# ir_homekit_1_0.net
KiCad netlist of a schematic drawn in EasyEDA
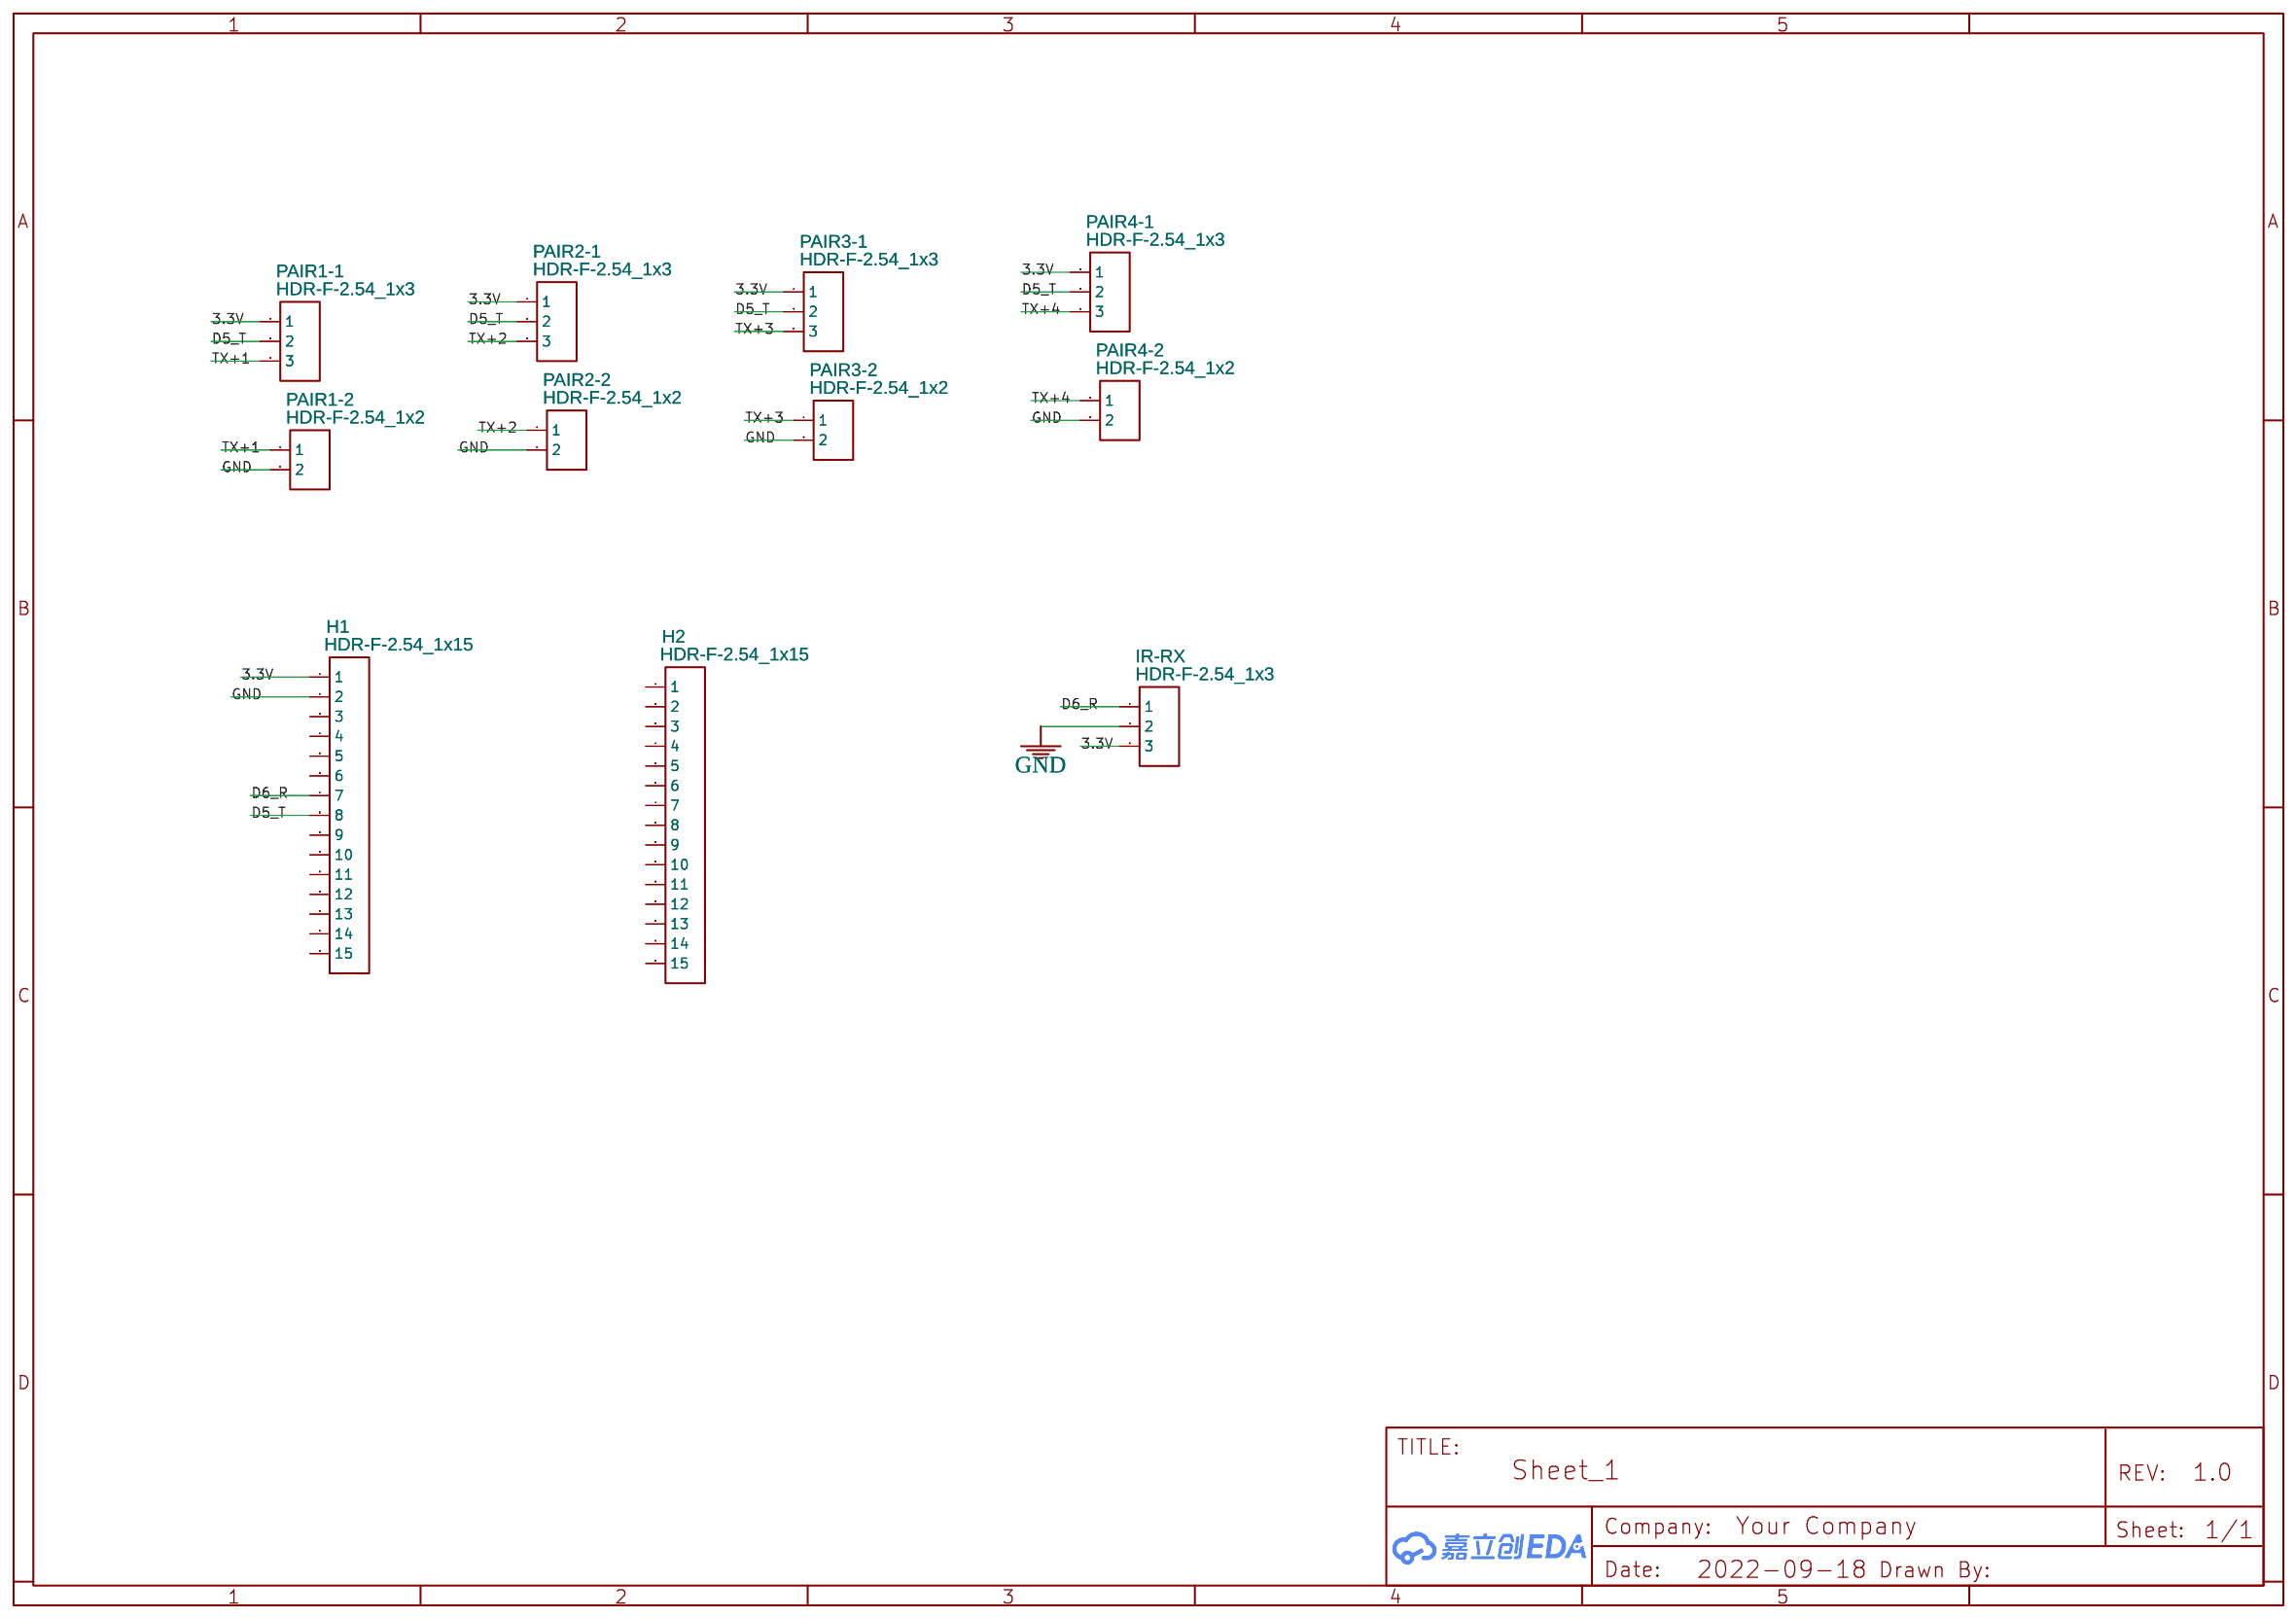
[diagram p0: schematic sheet]

(export (version "E")
  (design (tool "Eeschema 10.0.6"))
  (components
    (comp (ref "H1")
      (value "HDR-F-2.54_1x15")
      (fields (field (name "BOM_Supplier Part") "C124408"))
      (libsource (lib "") (part "HDR-F-2.54_1x15"))
    )
    (comp (ref "H2")
      (value "HDR-F-2.54_1x15")
      (fields (field (name "BOM_Supplier Part") "C124408"))
      (libsource (lib "") (part "HDR-F-2.54_1x15"))
    )
    (comp (ref "IR-RX")
      (value "HDR-F-2.54_1x3")
      (fields (field (name "BOM_Supplier Part") "C146690"))
      (libsource (lib "") (part "HDR-F-2.54_1x3_3"))
    )
    (comp (ref "PAIR1-1")
      (value "HDR-F-2.54_1x3")
      (fields (field (name "BOM_Supplier Part") "C146690"))
      (libsource (lib "") (part "HDR-F-2.54_1x3_2"))
    )
    (comp (ref "PAIR1-2")
      (value "HDR-F-2.54_1x2")
      (fields (field (name "BOM_Supplier Part") "C49661"))
      (libsource (lib "") (part "HDR-F-2.54_1x2_3"))
    )
    (comp (ref "PAIR2-1")
      (value "HDR-F-2.54_1x3")
      (fields (field (name "BOM_Supplier Part") "C146690"))
      (libsource (lib "") (part "HDR-F-2.54_1x3_4"))
    )
    (comp (ref "PAIR2-2")
      (value "HDR-F-2.54_1x2")
      (fields (field (name "BOM_Supplier Part") "C49661"))
      (libsource (lib "") (part "HDR-F-2.54_1x2"))
    )
    (comp (ref "PAIR3-1")
      (value "HDR-F-2.54_1x3")
      (fields (field (name "BOM_Supplier Part") "C146690"))
      (libsource (lib "") (part "HDR-F-2.54_1x3"))
    )
    (comp (ref "PAIR3-2")
      (value "HDR-F-2.54_1x2")
      (fields (field (name "BOM_Supplier Part") "C49661"))
      (libsource (lib "") (part "HDR-F-2.54_1x2_2"))
    )
    (comp (ref "PAIR4-1")
      (value "HDR-F-2.54_1x3")
      (fields (field (name "BOM_Supplier Part") "C146690"))
      (libsource (lib "") (part "HDR-F-2.54_1x3_1"))
    )
    (comp (ref "PAIR4-2")
      (value "HDR-F-2.54_1x2")
      (fields (field (name "BOM_Supplier Part") "C49661"))
      (libsource (lib "") (part "HDR-F-2.54_1x2_1"))
    )
  )
  (nets
    (net (code "1") (name "/3.3V") (class "Default")
      (node (ref "H1") (pin "1") (pinfunction "1_1") (pintype "unspecified"))
      (node (ref "IR-RX") (pin "3") (pinfunction "3_3") (pintype "input"))
      (node (ref "PAIR1-1") (pin "1") (pinfunction "1_1") (pintype "input"))
      (node (ref "PAIR2-1") (pin "1") (pinfunction "1_1") (pintype "input"))
      (node (ref "PAIR3-1") (pin "1") (pinfunction "1_1") (pintype "input"))
      (node (ref "PAIR4-1") (pin "1") (pinfunction "1_1") (pintype "input"))
    )
    (net (code "2") (name "/D5_T") (class "Default")
      (node (ref "H1") (pin "8") (pinfunction "8_8") (pintype "unspecified"))
      (node (ref "PAIR1-1") (pin "2") (pinfunction "2_2") (pintype "input"))
      (node (ref "PAIR2-1") (pin "2") (pinfunction "2_2") (pintype "input"))
      (node (ref "PAIR3-1") (pin "2") (pinfunction "2_2") (pintype "input"))
      (node (ref "PAIR4-1") (pin "2") (pinfunction "2_2") (pintype "input"))
    )
    (net (code "3") (name "/D6_R") (class "Default")
      (node (ref "H1") (pin "7") (pinfunction "7_7") (pintype "unspecified"))
      (node (ref "IR-RX") (pin "1") (pinfunction "1_1") (pintype "input"))
    )
    (net (code "4") (name "/TX+1") (class "Default")
      (node (ref "PAIR1-1") (pin "3") (pinfunction "3_3") (pintype "input"))
      (node (ref "PAIR1-2") (pin "1") (pinfunction "1_1") (pintype "input"))
    )
    (net (code "5") (name "/TX+2") (class "Default")
      (node (ref "PAIR2-1") (pin "3") (pinfunction "3_3") (pintype "input"))
      (node (ref "PAIR2-2") (pin "1") (pinfunction "1_1") (pintype "input"))
    )
    (net (code "6") (name "/TX+3") (class "Default")
      (node (ref "PAIR3-1") (pin "3") (pinfunction "3_3") (pintype "input"))
      (node (ref "PAIR3-2") (pin "1") (pinfunction "1_1") (pintype "input"))
    )
    (net (code "7") (name "/TX+4") (class "Default")
      (node (ref "PAIR4-1") (pin "3") (pinfunction "3_3") (pintype "input"))
      (node (ref "PAIR4-2") (pin "1") (pinfunction "1_1") (pintype "input"))
    )
    (net (code "8") (name "GND") (class "Default")
      (node (ref "H1") (pin "2") (pinfunction "2_2") (pintype "unspecified"))
      (node (ref "IR-RX") (pin "2") (pinfunction "2_2") (pintype "input"))
      (node (ref "PAIR1-2") (pin "2") (pinfunction "2_2") (pintype "input"))
      (node (ref "PAIR2-2") (pin "2") (pinfunction "2_2") (pintype "input"))
      (node (ref "PAIR3-2") (pin "2") (pinfunction "2_2") (pintype "input"))
      (node (ref "PAIR4-2") (pin "2") (pinfunction "2_2") (pintype "input"))
    )
    (net (code "9") (name "unconnected-(H1-Pad3)") (class "Default")
      (node (ref "H1") (pin "3") (pinfunction "3_3") (pintype "unspecified"))
    )
    (net (code "10") (name "unconnected-(H1-Pad4)") (class "Default")
      (node (ref "H1") (pin "4") (pinfunction "4_4") (pintype "unspecified"))
    )
    (net (code "11") (name "unconnected-(H1-Pad5)") (class "Default")
      (node (ref "H1") (pin "5") (pinfunction "5_5") (pintype "unspecified"))
    )
    (net (code "12") (name "unconnected-(H1-Pad6)") (class "Default")
      (node (ref "H1") (pin "6") (pinfunction "6_6") (pintype "unspecified"))
    )
    (net (code "13") (name "unconnected-(H1-Pad9)") (class "Default")
      (node (ref "H1") (pin "9") (pinfunction "9_9") (pintype "unspecified"))
    )
    (net (code "14") (name "unconnected-(H1-Pad10)") (class "Default")
      (node (ref "H1") (pin "10") (pinfunction "10_10") (pintype "unspecified"))
    )
    (net (code "15") (name "unconnected-(H1-Pad11)") (class "Default")
      (node (ref "H1") (pin "11") (pinfunction "11_11") (pintype "unspecified"))
    )
    (net (code "16") (name "unconnected-(H1-Pad12)") (class "Default")
      (node (ref "H1") (pin "12") (pinfunction "12_12") (pintype "unspecified"))
    )
    (net (code "17") (name "unconnected-(H1-Pad13)") (class "Default")
      (node (ref "H1") (pin "13") (pinfunction "13_13") (pintype "unspecified"))
    )
    (net (code "18") (name "unconnected-(H1-Pad14)") (class "Default")
      (node (ref "H1") (pin "14") (pinfunction "14_14") (pintype "unspecified"))
    )
    (net (code "19") (name "unconnected-(H1-Pad15)") (class "Default")
      (node (ref "H1") (pin "15") (pinfunction "15_15") (pintype "unspecified"))
    )
    (net (code "20") (name "unconnected-(H2-Pad1)") (class "Default")
      (node (ref "H2") (pin "1") (pinfunction "1_1") (pintype "unspecified"))
    )
    (net (code "21") (name "unconnected-(H2-Pad2)") (class "Default")
      (node (ref "H2") (pin "2") (pinfunction "2_2") (pintype "unspecified"))
    )
    (net (code "22") (name "unconnected-(H2-Pad3)") (class "Default")
      (node (ref "H2") (pin "3") (pinfunction "3_3") (pintype "unspecified"))
    )
    (net (code "23") (name "unconnected-(H2-Pad4)") (class "Default")
      (node (ref "H2") (pin "4") (pinfunction "4_4") (pintype "unspecified"))
    )
    (net (code "24") (name "unconnected-(H2-Pad5)") (class "Default")
      (node (ref "H2") (pin "5") (pinfunction "5_5") (pintype "unspecified"))
    )
    (net (code "25") (name "unconnected-(H2-Pad6)") (class "Default")
      (node (ref "H2") (pin "6") (pinfunction "6_6") (pintype "unspecified"))
    )
    (net (code "26") (name "unconnected-(H2-Pad7)") (class "Default")
      (node (ref "H2") (pin "7") (pinfunction "7_7") (pintype "unspecified"))
    )
    (net (code "27") (name "unconnected-(H2-Pad8)") (class "Default")
      (node (ref "H2") (pin "8") (pinfunction "8_8") (pintype "unspecified"))
    )
    (net (code "28") (name "unconnected-(H2-Pad9)") (class "Default")
      (node (ref "H2") (pin "9") (pinfunction "9_9") (pintype "unspecified"))
    )
    (net (code "29") (name "unconnected-(H2-Pad10)") (class "Default")
      (node (ref "H2") (pin "10") (pinfunction "10_10") (pintype "unspecified"))
    )
    (net (code "30") (name "unconnected-(H2-Pad11)") (class "Default")
      (node (ref "H2") (pin "11") (pinfunction "11_11") (pintype "unspecified"))
    )
    (net (code "31") (name "unconnected-(H2-Pad12)") (class "Default")
      (node (ref "H2") (pin "12") (pinfunction "12_12") (pintype "unspecified"))
    )
    (net (code "32") (name "unconnected-(H2-Pad13)") (class "Default")
      (node (ref "H2") (pin "13") (pinfunction "13_13") (pintype "unspecified"))
    )
    (net (code "33") (name "unconnected-(H2-Pad14)") (class "Default")
      (node (ref "H2") (pin "14") (pinfunction "14_14") (pintype "unspecified"))
    )
    (net (code "34") (name "unconnected-(H2-Pad15)") (class "Default")
      (node (ref "H2") (pin "15") (pinfunction "15_15") (pintype "unspecified"))
    )
  )
)
